# TikiLights.net
KiCad netlist of a schematic drawn in EAGLE
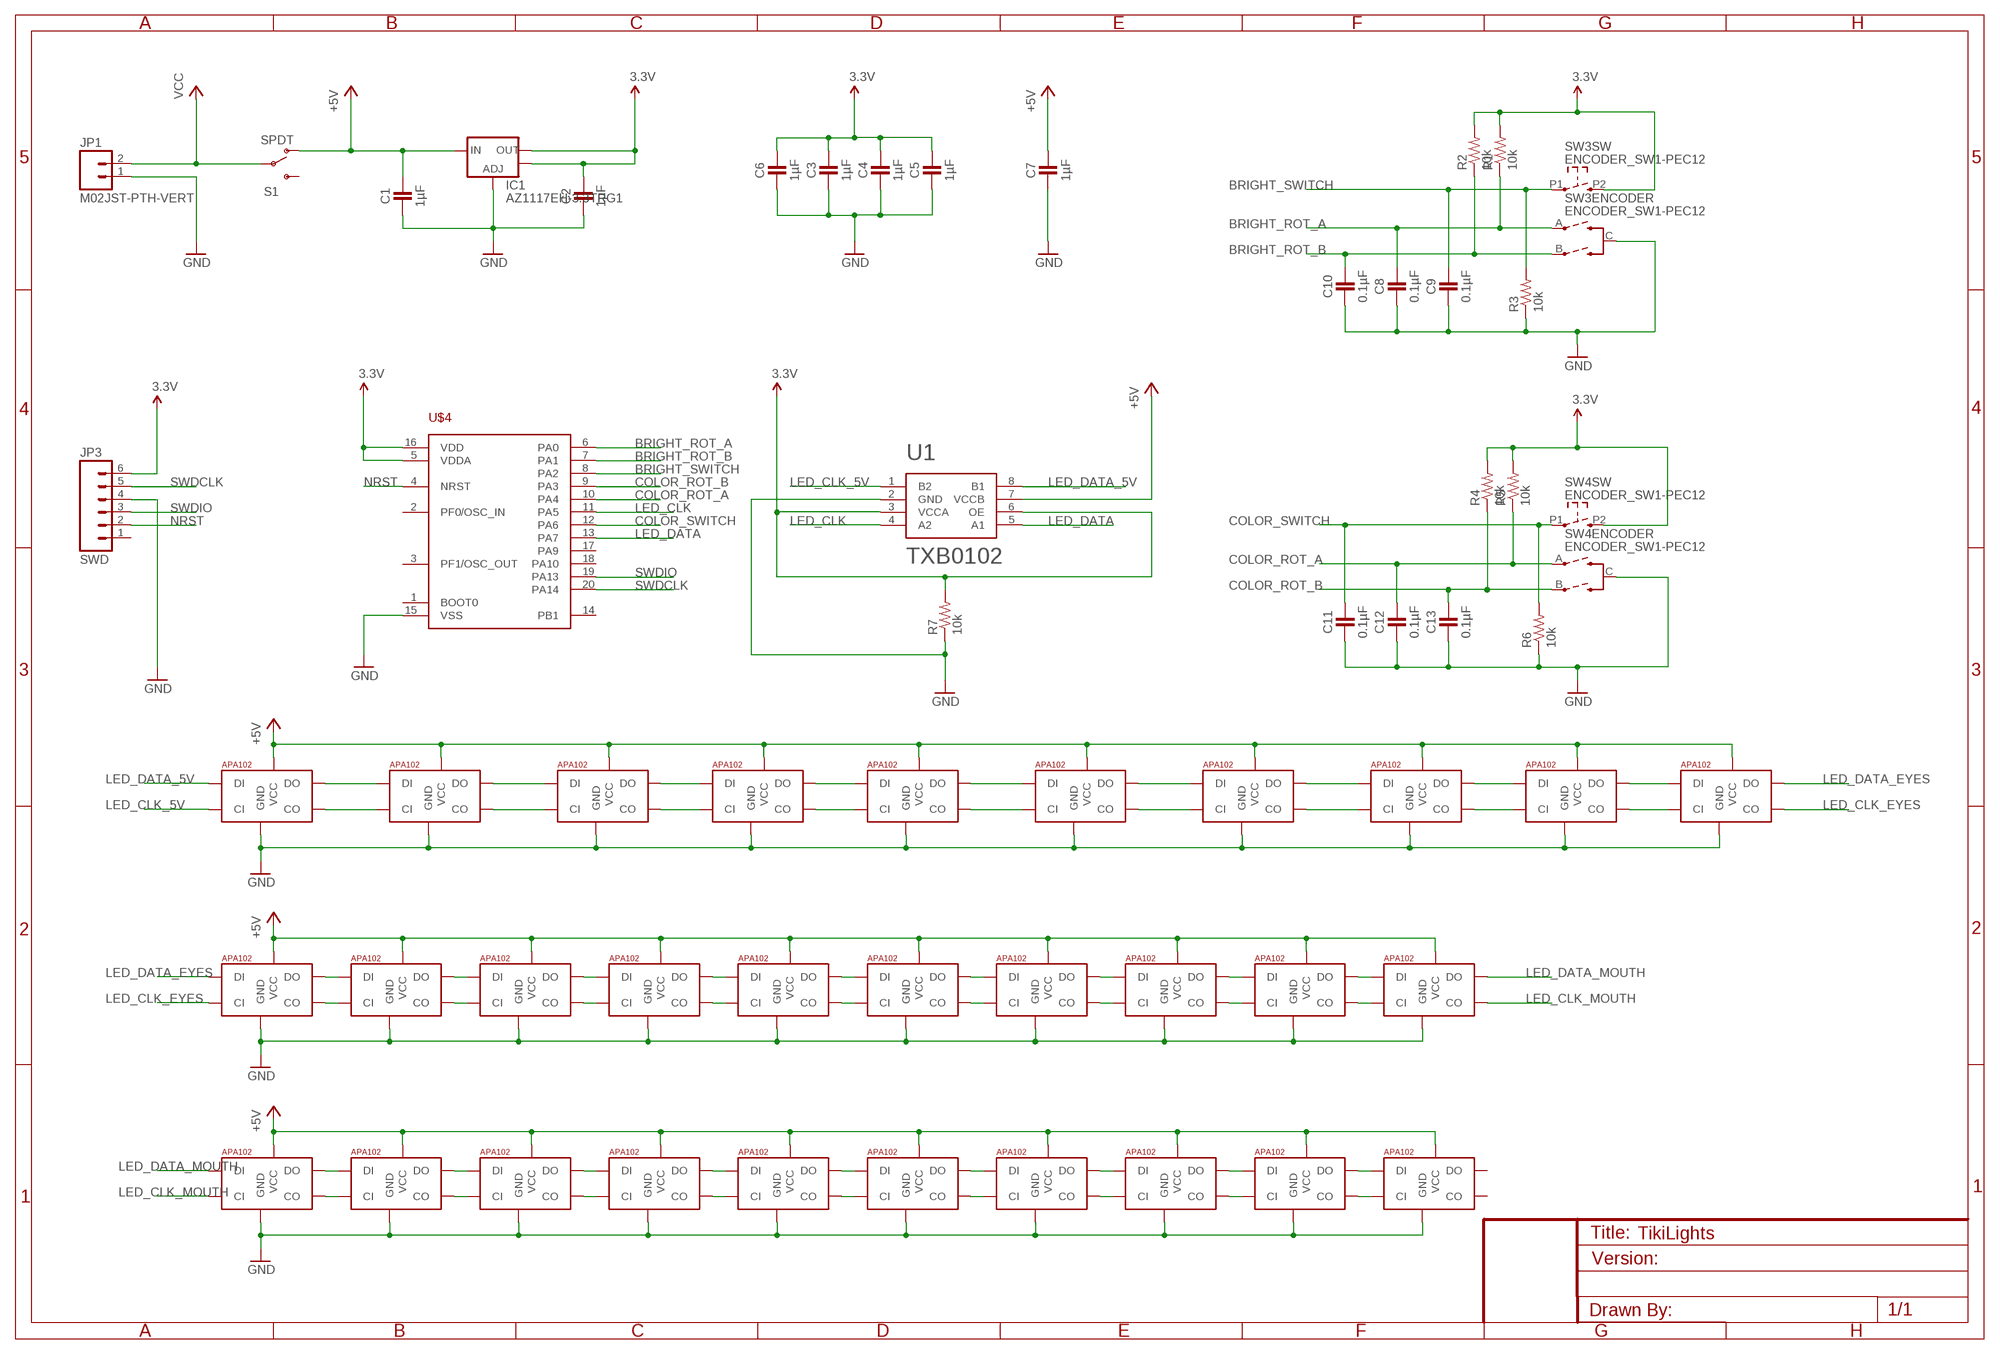
[diagram p0: schematic, sheet 1]

(export (version "E")
  (design (tool "Eeschema 10.0.6"))
  (components
    (comp (ref "C1")
      (value "1µF")
      (footprint "eagle-import:0603_CAP")
      (libsource (lib "eagle-import") (part "CAPACITOR0603_CAP"))
    )
    (comp (ref "C2")
      (value "1µF")
      (footprint "eagle-import:0603_CAP")
      (libsource (lib "eagle-import") (part "CAPACITOR0603_CAP"))
    )
    (comp (ref "C3")
      (value "1µF")
      (footprint "eagle-import:0603_CAP")
      (libsource (lib "eagle-import") (part "CAPACITOR0603_CAP"))
    )
    (comp (ref "C4")
      (value "1µF")
      (footprint "eagle-import:0603_CAP")
      (libsource (lib "eagle-import") (part "CAPACITOR0603_CAP"))
    )
    (comp (ref "C5")
      (value "1µF")
      (footprint "eagle-import:0603_CAP")
      (libsource (lib "eagle-import") (part "CAPACITOR0603_CAP"))
    )
    (comp (ref "C6")
      (value "1µF")
      (footprint "eagle-import:0603_CAP")
      (libsource (lib "eagle-import") (part "CAPACITOR0603_CAP"))
    )
    (comp (ref "C7")
      (value "1µF")
      (footprint "eagle-import:0603_CAP")
      (libsource (lib "eagle-import") (part "CAPACITOR0603_CAP"))
    )
    (comp (ref "C8")
      (value "0.1µF")
      (footprint "eagle-import:0603_CAP")
      (libsource (lib "eagle-import") (part "CAPACITOR0603_CAP"))
    )
    (comp (ref "C9")
      (value "0.1µF")
      (footprint "eagle-import:0603_CAP")
      (libsource (lib "eagle-import") (part "CAPACITOR0603_CAP"))
    )
    (comp (ref "C10")
      (value "0.1µF")
      (footprint "eagle-import:0603_CAP")
      (libsource (lib "eagle-import") (part "CAPACITOR0603_CAP"))
    )
    (comp (ref "C11")
      (value "0.1µF")
      (footprint "eagle-import:0603_CAP")
      (libsource (lib "eagle-import") (part "CAPACITOR0603_CAP"))
    )
    (comp (ref "C12")
      (value "0.1µF")
      (footprint "eagle-import:0603_CAP")
      (libsource (lib "eagle-import") (part "CAPACITOR0603_CAP"))
    )
    (comp (ref "C13")
      (value "0.1µF")
      (footprint "eagle-import:0603_CAP")
      (libsource (lib "eagle-import") (part "CAPACITOR0603_CAP"))
    )
    (comp (ref "IC1")
      (value "AZ1117EH-3.3TRG1")
      (footprint "eagle-import:SOT223")
      (libsource (lib "eagle-import") (part "V_REG_LM1117SOT223"))
    )
    (comp (ref "JP1")
      (value "M02JST-PTH-VERT")
      (footprint "eagle-import:JST-2-PTH-VERT")
      (libsource (lib "eagle-import") (part "M02JST-PTH-VERT"))
    )
    (comp (ref "JP3")
      (value "SWD")
      (footprint "eagle-import:MOLEX-1X6")
      (libsource (lib "eagle-import") (part "M06POLAR"))
    )
    (comp (ref "R1")
      (value "10k")
      (footprint "eagle-import:0603-RES")
      (libsource (lib "eagle-import") (part "RESISTOR0603"))
    )
    (comp (ref "R2")
      (value "10k")
      (footprint "eagle-import:0603-RES")
      (libsource (lib "eagle-import") (part "RESISTOR0603"))
    )
    (comp (ref "R3")
      (value "10k")
      (footprint "eagle-import:0603-RES")
      (libsource (lib "eagle-import") (part "RESISTOR0603"))
    )
    (comp (ref "R4")
      (value "10k")
      (footprint "eagle-import:0603-RES")
      (libsource (lib "eagle-import") (part "RESISTOR0603"))
    )
    (comp (ref "R5")
      (value "10k")
      (footprint "eagle-import:0603-RES")
      (libsource (lib "eagle-import") (part "RESISTOR0603"))
    )
    (comp (ref "R6")
      (value "10k")
      (footprint "eagle-import:0603-RES")
      (libsource (lib "eagle-import") (part "RESISTOR0603"))
    )
    (comp (ref "R7")
      (value "10k")
      (footprint "eagle-import:0603-RES")
      (libsource (lib "eagle-import") (part "RESISTOR0603"))
    )
    (comp (ref "S1")
      (value "SPDT")
      (footprint "eagle-import:SWITCH-SPDT")
      (libsource (lib "eagle-import") (part "SWITCH-SPDTPTH"))
    )
    (comp (ref "SW3")
      (value "ENCODER_SW1-PEC12")
      (footprint "eagle-import:PEC12_INCREMENTAL_ENCODER")
      (libsource (lib "eagle-import") (part "ENCODER_SW1-PEC12"))
    )
    (comp (ref "SW4")
      (value "ENCODER_SW1-PEC12")
      (footprint "eagle-import:PEC12_INCREMENTAL_ENCODER")
      (libsource (lib "eagle-import") (part "ENCODER_SW1-PEC12"))
    )
    (comp (ref "U$1")
      (value "APA1022020")
      (footprint "eagle-import:APA102_2020")
      (libsource (lib "eagle-import") (part "APA1022020"))
    )
    (comp (ref "U$2")
      (value "APA1022020")
      (footprint "eagle-import:APA102_2020")
      (libsource (lib "eagle-import") (part "APA1022020"))
    )
    (comp (ref "U$3")
      (value "APA1022020")
      (footprint "eagle-import:APA102_2020")
      (libsource (lib "eagle-import") (part "APA1022020"))
    )
    (comp (ref "U$4")
      (value "STM32F030F4")
      (footprint "eagle-import:TSSOP20")
      (libsource (lib "eagle-import") (part "STM32F030F4"))
    )
    (comp (ref "U$5")
      (value "APA1022020")
      (footprint "eagle-import:APA102_2020")
      (libsource (lib "eagle-import") (part "APA1022020"))
    )
    (comp (ref "U$6")
      (value "APA1022020")
      (footprint "eagle-import:APA102_2020")
      (libsource (lib "eagle-import") (part "APA1022020"))
    )
    (comp (ref "U$7")
      (value "APA1025050")
      (footprint "eagle-import:APA102_5050")
      (libsource (lib "eagle-import") (part "APA1025050"))
    )
    (comp (ref "U$8")
      (value "APA1025050")
      (footprint "eagle-import:APA102_5050")
      (libsource (lib "eagle-import") (part "APA1025050"))
    )
    (comp (ref "U$9")
      (value "APA1025050")
      (footprint "eagle-import:APA102_5050")
      (libsource (lib "eagle-import") (part "APA1025050"))
    )
    (comp (ref "U$10")
      (value "APA1025050")
      (footprint "eagle-import:APA102_5050")
      (libsource (lib "eagle-import") (part "APA1025050"))
    )
    (comp (ref "U$11")
      (value "APA1025050")
      (footprint "eagle-import:APA102_5050")
      (libsource (lib "eagle-import") (part "APA1025050"))
    )
    (comp (ref "U$12")
      (value "APA1025050")
      (footprint "eagle-import:APA102_5050")
      (libsource (lib "eagle-import") (part "APA1025050"))
    )
    (comp (ref "U$13")
      (value "APA1025050")
      (footprint "eagle-import:APA102_5050")
      (libsource (lib "eagle-import") (part "APA1025050"))
    )
    (comp (ref "U$14")
      (value "APA1025050")
      (footprint "eagle-import:APA102_5050")
      (libsource (lib "eagle-import") (part "APA1025050"))
    )
    (comp (ref "U$15")
      (value "APA1025050")
      (footprint "eagle-import:APA102_5050")
      (libsource (lib "eagle-import") (part "APA1025050"))
    )
    (comp (ref "U$16")
      (value "APA1025050")
      (footprint "eagle-import:APA102_5050")
      (libsource (lib "eagle-import") (part "APA1025050"))
    )
    (comp (ref "U$17")
      (value "APA1025050")
      (footprint "eagle-import:APA102_5050")
      (libsource (lib "eagle-import") (part "APA1025050"))
    )
    (comp (ref "U$18")
      (value "APA1025050")
      (footprint "eagle-import:APA102_5050")
      (libsource (lib "eagle-import") (part "APA1025050"))
    )
    (comp (ref "U$19")
      (value "APA1025050")
      (footprint "eagle-import:APA102_5050")
      (libsource (lib "eagle-import") (part "APA1025050"))
    )
    (comp (ref "U$20")
      (value "APA1025050")
      (footprint "eagle-import:APA102_5050")
      (libsource (lib "eagle-import") (part "APA1025050"))
    )
    (comp (ref "U$21")
      (value "APA1025050")
      (footprint "eagle-import:APA102_5050")
      (libsource (lib "eagle-import") (part "APA1025050"))
    )
    (comp (ref "U$22")
      (value "APA1025050")
      (footprint "eagle-import:APA102_5050")
      (libsource (lib "eagle-import") (part "APA1025050"))
    )
    (comp (ref "U$23")
      (value "APA1025050")
      (footprint "eagle-import:APA102_5050")
      (libsource (lib "eagle-import") (part "APA1025050"))
    )
    (comp (ref "U$24")
      (value "APA1025050")
      (footprint "eagle-import:APA102_5050")
      (libsource (lib "eagle-import") (part "APA1025050"))
    )
    (comp (ref "U$25")
      (value "APA1025050")
      (footprint "eagle-import:APA102_5050")
      (libsource (lib "eagle-import") (part "APA1025050"))
    )
    (comp (ref "U$26")
      (value "APA1025050")
      (footprint "eagle-import:APA102_5050")
      (libsource (lib "eagle-import") (part "APA1025050"))
    )
    (comp (ref "U$27")
      (value "APA1022020")
      (footprint "eagle-import:APA102_2020")
      (libsource (lib "eagle-import") (part "APA1022020"))
    )
    (comp (ref "U$28")
      (value "APA1022020")
      (footprint "eagle-import:APA102_2020")
      (libsource (lib "eagle-import") (part "APA1022020"))
    )
    (comp (ref "U$29")
      (value "APA1022020")
      (footprint "eagle-import:APA102_2020")
      (libsource (lib "eagle-import") (part "APA1022020"))
    )
    (comp (ref "U$30")
      (value "APA1022020")
      (footprint "eagle-import:APA102_2020")
      (libsource (lib "eagle-import") (part "APA1022020"))
    )
    (comp (ref "U$31")
      (value "APA1022020")
      (footprint "eagle-import:APA102_2020")
      (libsource (lib "eagle-import") (part "APA1022020"))
    )
    (comp (ref "U1")
      (value "TXB0102")
      (footprint "eagle-import:SOP50P310X90-8N")
      (fields (field (name "MF") "Texas Instruments"))
      (libsource (lib "eagle-import") (part "TXB0102"))
    )
  )
  (nets
    (net (code "1") (name "+5V") (class "Default")
      (node (ref "C1") (pin "1") (pinfunction "1_1") (pintype "bidirectional"))
      (node (ref "C7") (pin "1") (pinfunction "1_1") (pintype "bidirectional"))
      (node (ref "IC1") (pin "3") (pinfunction "IN_3") (pintype "input"))
      (node (ref "S1") (pin "1") (pinfunction "O_1") (pintype "passive"))
      (node (ref "U$1") (pin "V_CC") (pinfunction "VCC_V_CC") (pintype "bidirectional"))
      (node (ref "U$10") (pin "1") (pinfunction "VCC_1") (pintype "bidirectional"))
      (node (ref "U$11") (pin "1") (pinfunction "VCC_1") (pintype "bidirectional"))
      (node (ref "U$12") (pin "1") (pinfunction "VCC_1") (pintype "bidirectional"))
      (node (ref "U$13") (pin "1") (pinfunction "VCC_1") (pintype "bidirectional"))
      (node (ref "U$14") (pin "1") (pinfunction "VCC_1") (pintype "bidirectional"))
      (node (ref "U$15") (pin "1") (pinfunction "VCC_1") (pintype "bidirectional"))
      (node (ref "U$16") (pin "1") (pinfunction "VCC_1") (pintype "bidirectional"))
      (node (ref "U$17") (pin "1") (pinfunction "VCC_1") (pintype "bidirectional"))
      (node (ref "U$18") (pin "1") (pinfunction "VCC_1") (pintype "bidirectional"))
      (node (ref "U$19") (pin "1") (pinfunction "VCC_1") (pintype "bidirectional"))
      (node (ref "U$2") (pin "V_CC") (pinfunction "VCC_V_CC") (pintype "bidirectional"))
      (node (ref "U$20") (pin "1") (pinfunction "VCC_1") (pintype "bidirectional"))
      (node (ref "U$21") (pin "1") (pinfunction "VCC_1") (pintype "bidirectional"))
      (node (ref "U$22") (pin "1") (pinfunction "VCC_1") (pintype "bidirectional"))
      (node (ref "U$23") (pin "1") (pinfunction "VCC_1") (pintype "bidirectional"))
      (node (ref "U$24") (pin "1") (pinfunction "VCC_1") (pintype "bidirectional"))
      (node (ref "U$25") (pin "1") (pinfunction "VCC_1") (pintype "bidirectional"))
      (node (ref "U$26") (pin "1") (pinfunction "VCC_1") (pintype "bidirectional"))
      (node (ref "U$27") (pin "V_CC") (pinfunction "VCC_V_CC") (pintype "bidirectional"))
      (node (ref "U$28") (pin "V_CC") (pinfunction "VCC_V_CC") (pintype "bidirectional"))
      (node (ref "U$29") (pin "V_CC") (pinfunction "VCC_V_CC") (pintype "bidirectional"))
      (node (ref "U$3") (pin "V_CC") (pinfunction "VCC_V_CC") (pintype "bidirectional"))
      (node (ref "U$30") (pin "V_CC") (pinfunction "VCC_V_CC") (pintype "bidirectional"))
      (node (ref "U$31") (pin "V_CC") (pinfunction "VCC_V_CC") (pintype "bidirectional"))
      (node (ref "U$5") (pin "V_CC") (pinfunction "VCC_V_CC") (pintype "bidirectional"))
      (node (ref "U$6") (pin "V_CC") (pinfunction "VCC_V_CC") (pintype "bidirectional"))
      (node (ref "U$7") (pin "1") (pinfunction "VCC_1") (pintype "bidirectional"))
      (node (ref "U$8") (pin "1") (pinfunction "VCC_1") (pintype "bidirectional"))
      (node (ref "U$9") (pin "1") (pinfunction "VCC_1") (pintype "bidirectional"))
      (node (ref "U1") (pin "7") (pinfunction "VCCB_7") (pintype "bidirectional"))
    )
    (net (code "2") (name "/BRIGHT_ROT_A") (class "Default")
      (node (ref "C8") (pin "1") (pinfunction "1_1") (pintype "bidirectional"))
      (node (ref "R1") (pin "1") (pinfunction "1_1") (pintype "passive"))
      (node (ref "SW3") (pin "A") (pinfunction "A_A") (pintype "passive"))
      (node (ref "U$4") (pin "6") (pinfunction "PA0_6") (pintype "bidirectional"))
    )
    (net (code "3") (name "/BRIGHT_ROT_B") (class "Default")
      (node (ref "C10") (pin "1") (pinfunction "1_1") (pintype "bidirectional"))
      (node (ref "R2") (pin "1") (pinfunction "1_1") (pintype "passive"))
      (node (ref "SW3") (pin "B") (pinfunction "B_B") (pintype "passive"))
      (node (ref "U$4") (pin "7") (pinfunction "PA1_7") (pintype "bidirectional"))
    )
    (net (code "4") (name "/BRIGHT_SWITCH") (class "Default")
      (node (ref "C9") (pin "1") (pinfunction "1_1") (pintype "bidirectional"))
      (node (ref "R3") (pin "2") (pinfunction "2_2") (pintype "passive"))
      (node (ref "SW3") (pin "P1") (pinfunction "1_P1") (pintype "passive"))
      (node (ref "U$4") (pin "8") (pinfunction "PA2_8") (pintype "bidirectional"))
    )
    (net (code "5") (name "/COLOR_ROT_A") (class "Default")
      (node (ref "C12") (pin "1") (pinfunction "1_1") (pintype "bidirectional"))
      (node (ref "R5") (pin "1") (pinfunction "1_1") (pintype "passive"))
      (node (ref "SW4") (pin "A") (pinfunction "A_A") (pintype "passive"))
      (node (ref "U$4") (pin "10") (pinfunction "PA4_10") (pintype "bidirectional"))
    )
    (net (code "6") (name "/COLOR_ROT_B") (class "Default")
      (node (ref "C13") (pin "1") (pinfunction "1_1") (pintype "bidirectional"))
      (node (ref "R4") (pin "1") (pinfunction "1_1") (pintype "passive"))
      (node (ref "SW4") (pin "B") (pinfunction "B_B") (pintype "passive"))
      (node (ref "U$4") (pin "9") (pinfunction "PA3_9") (pintype "bidirectional"))
    )
    (net (code "7") (name "/COLOR_SWITCH") (class "Default")
      (node (ref "C11") (pin "1") (pinfunction "1_1") (pintype "bidirectional"))
      (node (ref "R6") (pin "2") (pinfunction "2_2") (pintype "passive"))
      (node (ref "SW4") (pin "P1") (pinfunction "1_P1") (pintype "passive"))
      (node (ref "U$4") (pin "12") (pinfunction "PA6_12") (pintype "bidirectional"))
    )
    (net (code "8") (name "/LED_CLK") (class "Default")
      (node (ref "U$4") (pin "11") (pinfunction "PA5_11") (pintype "bidirectional"))
      (node (ref "U1") (pin "4") (pinfunction "A2_4") (pintype "bidirectional"))
    )
    (net (code "9") (name "/LED_CLK_5V") (class "Default")
      (node (ref "U$1") (pin "C_IN") (pinfunction "CI_C_IN") (pintype "bidirectional"))
      (node (ref "U1") (pin "1") (pinfunction "B2_1") (pintype "bidirectional"))
    )
    (net (code "10") (name "/LED_CLK_EYES") (class "Default")
      (node (ref "U$31") (pin "CL_OUT") (pinfunction "CO_CL_OUT") (pintype "bidirectional"))
      (node (ref "U$7") (pin "5") (pinfunction "CI_5") (pintype "bidirectional"))
    )
    (net (code "11") (name "/LED_CLK_MOUTH") (class "Default")
      (node (ref "U$16") (pin "2") (pinfunction "CO_2") (pintype "bidirectional"))
      (node (ref "U$17") (pin "5") (pinfunction "CI_5") (pintype "bidirectional"))
    )
    (net (code "12") (name "/LED_DATA") (class "Default")
      (node (ref "U$4") (pin "13") (pinfunction "PA7_13") (pintype "bidirectional"))
      (node (ref "U1") (pin "5") (pinfunction "A1_5") (pintype "bidirectional"))
    )
    (net (code "13") (name "/LED_DATA_5V") (class "Default")
      (node (ref "U$1") (pin "D_IN") (pinfunction "DI_D_IN") (pintype "bidirectional"))
      (node (ref "U1") (pin "8") (pinfunction "B1_8") (pintype "bidirectional"))
    )
    (net (code "14") (name "/LED_DATA_EYES") (class "Default")
      (node (ref "U$31") (pin "D_OUT") (pinfunction "DO_D_OUT") (pintype "bidirectional"))
      (node (ref "U$7") (pin "4") (pinfunction "DI_4") (pintype "bidirectional"))
    )
    (net (code "15") (name "/LED_DATA_MOUTH") (class "Default")
      (node (ref "U$16") (pin "3") (pinfunction "DO_3") (pintype "bidirectional"))
      (node (ref "U$17") (pin "4") (pinfunction "DI_4") (pintype "bidirectional"))
    )
    (net (code "16") (name "/NRST") (class "Default")
      (node (ref "JP3") (pin "2") (pinfunction "2_2") (pintype "passive"))
      (node (ref "U$4") (pin "4") (pinfunction "NRST_4") (pintype "bidirectional"))
    )
    (net (code "17") (name "/SWDCLK") (class "Default")
      (node (ref "JP3") (pin "5") (pinfunction "5_5") (pintype "passive"))
      (node (ref "U$4") (pin "20") (pinfunction "PA14_20") (pintype "bidirectional"))
    )
    (net (code "18") (name "/SWDIO") (class "Default")
      (node (ref "JP3") (pin "3") (pinfunction "3_3") (pintype "passive"))
      (node (ref "U$4") (pin "19") (pinfunction "PA13_19") (pintype "bidirectional"))
    )
    (net (code "19") (name "3.3V") (class "Default")
      (node (ref "C2") (pin "1") (pinfunction "1_1") (pintype "bidirectional"))
      (node (ref "C3") (pin "1") (pinfunction "1_1") (pintype "bidirectional"))
      (node (ref "C4") (pin "1") (pinfunction "1_1") (pintype "bidirectional"))
      (node (ref "C5") (pin "1") (pinfunction "1_1") (pintype "bidirectional"))
      (node (ref "C6") (pin "1") (pinfunction "1_1") (pintype "bidirectional"))
      (node (ref "IC1") (pin "2") (pinfunction "OUT_2") (pintype "output"))
      (node (ref "IC1") (pin "4") (pinfunction "OUT_4") (pintype "output"))
      (node (ref "JP3") (pin "6") (pinfunction "6_6") (pintype "passive"))
      (node (ref "R1") (pin "2") (pinfunction "2_2") (pintype "passive"))
      (node (ref "R2") (pin "2") (pinfunction "2_2") (pintype "passive"))
      (node (ref "R4") (pin "2") (pinfunction "2_2") (pintype "passive"))
      (node (ref "R5") (pin "2") (pinfunction "2_2") (pintype "passive"))
      (node (ref "R7") (pin "2") (pinfunction "2_2") (pintype "passive"))
      (node (ref "SW3") (pin "P2") (pinfunction "2_P2") (pintype "passive"))
      (node (ref "SW4") (pin "P2") (pinfunction "2_P2") (pintype "passive"))
      (node (ref "U$4") (pin "16") (pinfunction "VDD_16") (pintype "bidirectional"))
      (node (ref "U$4") (pin "5") (pinfunction "VDDA_5") (pintype "bidirectional"))
      (node (ref "U1") (pin "3") (pinfunction "VCCA_3") (pintype "bidirectional"))
      (node (ref "U1") (pin "6") (pinfunction "OE_6") (pintype "bidirectional"))
    )
    (net (code "20") (name "GND") (class "Default")
      (node (ref "C1") (pin "2") (pinfunction "2_2") (pintype "bidirectional"))
      (node (ref "C10") (pin "2") (pinfunction "2_2") (pintype "bidirectional"))
      (node (ref "C11") (pin "2") (pinfunction "2_2") (pintype "bidirectional"))
      (node (ref "C12") (pin "2") (pinfunction "2_2") (pintype "bidirectional"))
      (node (ref "C13") (pin "2") (pinfunction "2_2") (pintype "bidirectional"))
      (node (ref "C2") (pin "2") (pinfunction "2_2") (pintype "bidirectional"))
      (node (ref "C3") (pin "2") (pinfunction "2_2") (pintype "bidirectional"))
      (node (ref "C4") (pin "2") (pinfunction "2_2") (pintype "bidirectional"))
      (node (ref "C5") (pin "2") (pinfunction "2_2") (pintype "bidirectional"))
      (node (ref "C6") (pin "2") (pinfunction "2_2") (pintype "bidirectional"))
      (node (ref "C7") (pin "2") (pinfunction "2_2") (pintype "bidirectional"))
      (node (ref "C8") (pin "2") (pinfunction "2_2") (pintype "bidirectional"))
      (node (ref "C9") (pin "2") (pinfunction "2_2") (pintype "bidirectional"))
      (node (ref "IC1") (pin "1") (pinfunction "ADJ_1") (pintype "input"))
      (node (ref "JP1") (pin "1") (pinfunction "1_1") (pintype "passive"))
      (node (ref "JP3") (pin "4") (pinfunction "4_4") (pintype "passive"))
      (node (ref "R3") (pin "1") (pinfunction "1_1") (pintype "passive"))
      (node (ref "R6") (pin "1") (pinfunction "1_1") (pintype "passive"))
      (node (ref "R7") (pin "1") (pinfunction "1_1") (pintype "passive"))
      (node (ref "SW3") (pin "C") (pinfunction "C_C") (pintype "passive"))
      (node (ref "SW4") (pin "C") (pinfunction "C_C") (pintype "passive"))
      (node (ref "U$1") (pin "GND") (pinfunction "GND_GND") (pintype "bidirectional"))
      (node (ref "U$10") (pin "6") (pinfunction "GND_6") (pintype "bidirectional"))
      (node (ref "U$11") (pin "6") (pinfunction "GND_6") (pintype "bidirectional"))
      (node (ref "U$12") (pin "6") (pinfunction "GND_6") (pintype "bidirectional"))
      (node (ref "U$13") (pin "6") (pinfunction "GND_6") (pintype "bidirectional"))
      (node (ref "U$14") (pin "6") (pinfunction "GND_6") (pintype "bidirectional"))
      (node (ref "U$15") (pin "6") (pinfunction "GND_6") (pintype "bidirectional"))
      (node (ref "U$16") (pin "6") (pinfunction "GND_6") (pintype "bidirectional"))
      (node (ref "U$17") (pin "6") (pinfunction "GND_6") (pintype "bidirectional"))
      (node (ref "U$18") (pin "6") (pinfunction "GND_6") (pintype "bidirectional"))
      (node (ref "U$19") (pin "6") (pinfunction "GND_6") (pintype "bidirectional"))
      (node (ref "U$2") (pin "GND") (pinfunction "GND_GND") (pintype "bidirectional"))
      (node (ref "U$20") (pin "6") (pinfunction "GND_6") (pintype "bidirectional"))
      (node (ref "U$21") (pin "6") (pinfunction "GND_6") (pintype "bidirectional"))
      (node (ref "U$22") (pin "6") (pinfunction "GND_6") (pintype "bidirectional"))
      (node (ref "U$23") (pin "6") (pinfunction "GND_6") (pintype "bidirectional"))
      (node (ref "U$24") (pin "6") (pinfunction "GND_6") (pintype "bidirectional"))
      (node (ref "U$25") (pin "6") (pinfunction "GND_6") (pintype "bidirectional"))
      (node (ref "U$26") (pin "6") (pinfunction "GND_6") (pintype "bidirectional"))
      (node (ref "U$27") (pin "GND") (pinfunction "GND_GND") (pintype "bidirectional"))
      (node (ref "U$28") (pin "GND") (pinfunction "GND_GND") (pintype "bidirectional"))
      (node (ref "U$29") (pin "GND") (pinfunction "GND_GND") (pintype "bidirectional"))
      (node (ref "U$3") (pin "GND") (pinfunction "GND_GND") (pintype "bidirectional"))
      (node (ref "U$30") (pin "GND") (pinfunction "GND_GND") (pintype "bidirectional"))
      (node (ref "U$31") (pin "GND") (pinfunction "GND_GND") (pintype "bidirectional"))
      (node (ref "U$4") (pin "15") (pinfunction "VSS_15") (pintype "bidirectional"))
      (node (ref "U$5") (pin "GND") (pinfunction "GND_GND") (pintype "bidirectional"))
      (node (ref "U$6") (pin "GND") (pinfunction "GND_GND") (pintype "bidirectional"))
      (node (ref "U$7") (pin "6") (pinfunction "GND_6") (pintype "bidirectional"))
      (node (ref "U$8") (pin "6") (pinfunction "GND_6") (pintype "bidirectional"))
      (node (ref "U$9") (pin "6") (pinfunction "GND_6") (pintype "bidirectional"))
      (node (ref "U1") (pin "2") (pinfunction "GND_2") (pintype "bidirectional"))
    )
    (net (code "21") (name "Net-(U$1-CO)") (class "Default")
      (node (ref "U$1") (pin "CL_OUT") (pinfunction "CO_CL_OUT") (pintype "bidirectional"))
      (node (ref "U$2") (pin "C_IN") (pinfunction "CI_C_IN") (pintype "bidirectional"))
    )
    (net (code "22") (name "Net-(U$1-DO)") (class "Default")
      (node (ref "U$1") (pin "D_OUT") (pinfunction "DO_D_OUT") (pintype "bidirectional"))
      (node (ref "U$2") (pin "D_IN") (pinfunction "DI_D_IN") (pintype "bidirectional"))
    )
    (net (code "23") (name "Net-(U$2-CO)") (class "Default")
      (node (ref "U$2") (pin "CL_OUT") (pinfunction "CO_CL_OUT") (pintype "bidirectional"))
      (node (ref "U$3") (pin "C_IN") (pinfunction "CI_C_IN") (pintype "bidirectional"))
    )
    (net (code "24") (name "Net-(U$2-DO)") (class "Default")
      (node (ref "U$2") (pin "D_OUT") (pinfunction "DO_D_OUT") (pintype "bidirectional"))
      (node (ref "U$3") (pin "D_IN") (pinfunction "DI_D_IN") (pintype "bidirectional"))
    )
    (net (code "25") (name "Net-(U$3-CO)") (class "Default")
      (node (ref "U$3") (pin "CL_OUT") (pinfunction "CO_CL_OUT") (pintype "bidirectional"))
      (node (ref "U$5") (pin "C_IN") (pinfunction "CI_C_IN") (pintype "bidirectional"))
    )
    (net (code "26") (name "Net-(U$3-DO)") (class "Default")
      (node (ref "U$3") (pin "D_OUT") (pinfunction "DO_D_OUT") (pintype "bidirectional"))
      (node (ref "U$5") (pin "D_IN") (pinfunction "DI_D_IN") (pintype "bidirectional"))
    )
    (net (code "27") (name "Net-(U$5-CO)") (class "Default")
      (node (ref "U$5") (pin "CL_OUT") (pinfunction "CO_CL_OUT") (pintype "bidirectional"))
      (node (ref "U$6") (pin "C_IN") (pinfunction "CI_C_IN") (pintype "bidirectional"))
    )
    (net (code "28") (name "Net-(U$5-DO)") (class "Default")
      (node (ref "U$5") (pin "D_OUT") (pinfunction "DO_D_OUT") (pintype "bidirectional"))
      (node (ref "U$6") (pin "D_IN") (pinfunction "DI_D_IN") (pintype "bidirectional"))
    )
    (net (code "29") (name "Net-(U$7-CO)") (class "Default")
      (node (ref "U$7") (pin "2") (pinfunction "CO_2") (pintype "bidirectional"))
      (node (ref "U$8") (pin "5") (pinfunction "CI_5") (pintype "bidirectional"))
    )
    (net (code "30") (name "Net-(U$7-DO)") (class "Default")
      (node (ref "U$7") (pin "3") (pinfunction "DO_3") (pintype "bidirectional"))
      (node (ref "U$8") (pin "4") (pinfunction "DI_4") (pintype "bidirectional"))
    )
    (net (code "31") (name "Net-(U$8-CO)") (class "Default")
      (node (ref "U$8") (pin "2") (pinfunction "CO_2") (pintype "bidirectional"))
      (node (ref "U$9") (pin "5") (pinfunction "CI_5") (pintype "bidirectional"))
    )
    (net (code "32") (name "Net-(U$8-DO)") (class "Default")
      (node (ref "U$8") (pin "3") (pinfunction "DO_3") (pintype "bidirectional"))
      (node (ref "U$9") (pin "4") (pinfunction "DI_4") (pintype "bidirectional"))
    )
    (net (code "33") (name "Net-(U$10-CI)") (class "Default")
      (node (ref "U$10") (pin "5") (pinfunction "CI_5") (pintype "bidirectional"))
      (node (ref "U$9") (pin "2") (pinfunction "CO_2") (pintype "bidirectional"))
    )
    (net (code "34") (name "Net-(U$10-CO)") (class "Default")
      (node (ref "U$10") (pin "2") (pinfunction "CO_2") (pintype "bidirectional"))
      (node (ref "U$11") (pin "5") (pinfunction "CI_5") (pintype "bidirectional"))
    )
    (net (code "35") (name "Net-(U$10-DI)") (class "Default")
      (node (ref "U$10") (pin "4") (pinfunction "DI_4") (pintype "bidirectional"))
      (node (ref "U$9") (pin "3") (pinfunction "DO_3") (pintype "bidirectional"))
    )
    (net (code "36") (name "Net-(U$10-DO)") (class "Default")
      (node (ref "U$10") (pin "3") (pinfunction "DO_3") (pintype "bidirectional"))
      (node (ref "U$11") (pin "4") (pinfunction "DI_4") (pintype "bidirectional"))
    )
    (net (code "37") (name "Net-(U$11-CO)") (class "Default")
      (node (ref "U$11") (pin "2") (pinfunction "CO_2") (pintype "bidirectional"))
      (node (ref "U$12") (pin "5") (pinfunction "CI_5") (pintype "bidirectional"))
    )
    (net (code "38") (name "Net-(U$11-DO)") (class "Default")
      (node (ref "U$11") (pin "3") (pinfunction "DO_3") (pintype "bidirectional"))
      (node (ref "U$12") (pin "4") (pinfunction "DI_4") (pintype "bidirectional"))
    )
    (net (code "39") (name "Net-(U$12-CO)") (class "Default")
      (node (ref "U$12") (pin "2") (pinfunction "CO_2") (pintype "bidirectional"))
      (node (ref "U$13") (pin "5") (pinfunction "CI_5") (pintype "bidirectional"))
    )
    (net (code "40") (name "Net-(U$12-DO)") (class "Default")
      (node (ref "U$12") (pin "3") (pinfunction "DO_3") (pintype "bidirectional"))
      (node (ref "U$13") (pin "4") (pinfunction "DI_4") (pintype "bidirectional"))
    )
    (net (code "41") (name "Net-(U$13-CO)") (class "Default")
      (node (ref "U$13") (pin "2") (pinfunction "CO_2") (pintype "bidirectional"))
      (node (ref "U$14") (pin "5") (pinfunction "CI_5") (pintype "bidirectional"))
    )
    (net (code "42") (name "Net-(U$13-DO)") (class "Default")
      (node (ref "U$13") (pin "3") (pinfunction "DO_3") (pintype "bidirectional"))
      (node (ref "U$14") (pin "4") (pinfunction "DI_4") (pintype "bidirectional"))
    )
    (net (code "43") (name "Net-(U$14-CO)") (class "Default")
      (node (ref "U$14") (pin "2") (pinfunction "CO_2") (pintype "bidirectional"))
      (node (ref "U$15") (pin "5") (pinfunction "CI_5") (pintype "bidirectional"))
    )
    (net (code "44") (name "Net-(U$14-DO)") (class "Default")
      (node (ref "U$14") (pin "3") (pinfunction "DO_3") (pintype "bidirectional"))
      (node (ref "U$15") (pin "4") (pinfunction "DI_4") (pintype "bidirectional"))
    )
    (net (code "45") (name "Net-(U$15-CO)") (class "Default")
      (node (ref "U$15") (pin "2") (pinfunction "CO_2") (pintype "bidirectional"))
      (node (ref "U$16") (pin "5") (pinfunction "CI_5") (pintype "bidirectional"))
    )
    (net (code "46") (name "Net-(U$15-DO)") (class "Default")
      (node (ref "U$15") (pin "3") (pinfunction "DO_3") (pintype "bidirectional"))
      (node (ref "U$16") (pin "4") (pinfunction "DI_4") (pintype "bidirectional"))
    )
    (net (code "47") (name "Net-(U$17-CO)") (class "Default")
      (node (ref "U$17") (pin "2") (pinfunction "CO_2") (pintype "bidirectional"))
      (node (ref "U$18") (pin "5") (pinfunction "CI_5") (pintype "bidirectional"))
    )
    (net (code "48") (name "Net-(U$17-DO)") (class "Default")
      (node (ref "U$17") (pin "3") (pinfunction "DO_3") (pintype "bidirectional"))
      (node (ref "U$18") (pin "4") (pinfunction "DI_4") (pintype "bidirectional"))
    )
    (net (code "49") (name "Net-(U$18-CO)") (class "Default")
      (node (ref "U$18") (pin "2") (pinfunction "CO_2") (pintype "bidirectional"))
      (node (ref "U$19") (pin "5") (pinfunction "CI_5") (pintype "bidirectional"))
    )
    (net (code "50") (name "Net-(U$18-DO)") (class "Default")
      (node (ref "U$18") (pin "3") (pinfunction "DO_3") (pintype "bidirectional"))
      (node (ref "U$19") (pin "4") (pinfunction "DI_4") (pintype "bidirectional"))
    )
    (net (code "51") (name "Net-(U$19-CO)") (class "Default")
      (node (ref "U$19") (pin "2") (pinfunction "CO_2") (pintype "bidirectional"))
      (node (ref "U$20") (pin "5") (pinfunction "CI_5") (pintype "bidirectional"))
    )
    (net (code "52") (name "Net-(U$19-DO)") (class "Default")
      (node (ref "U$19") (pin "3") (pinfunction "DO_3") (pintype "bidirectional"))
      (node (ref "U$20") (pin "4") (pinfunction "DI_4") (pintype "bidirectional"))
    )
    (net (code "53") (name "Net-(U$20-CO)") (class "Default")
      (node (ref "U$20") (pin "2") (pinfunction "CO_2") (pintype "bidirectional"))
      (node (ref "U$21") (pin "5") (pinfunction "CI_5") (pintype "bidirectional"))
    )
    (net (code "54") (name "Net-(U$20-DO)") (class "Default")
      (node (ref "U$20") (pin "3") (pinfunction "DO_3") (pintype "bidirectional"))
      (node (ref "U$21") (pin "4") (pinfunction "DI_4") (pintype "bidirectional"))
    )
    (net (code "55") (name "Net-(U$21-CO)") (class "Default")
      (node (ref "U$21") (pin "2") (pinfunction "CO_2") (pintype "bidirectional"))
      (node (ref "U$22") (pin "5") (pinfunction "CI_5") (pintype "bidirectional"))
    )
    (net (code "56") (name "Net-(U$21-DO)") (class "Default")
      (node (ref "U$21") (pin "3") (pinfunction "DO_3") (pintype "bidirectional"))
      (node (ref "U$22") (pin "4") (pinfunction "DI_4") (pintype "bidirectional"))
    )
    (net (code "57") (name "Net-(U$22-CO)") (class "Default")
      (node (ref "U$22") (pin "2") (pinfunction "CO_2") (pintype "bidirectional"))
      (node (ref "U$23") (pin "5") (pinfunction "CI_5") (pintype "bidirectional"))
    )
    (net (code "58") (name "Net-(U$22-DO)") (class "Default")
      (node (ref "U$22") (pin "3") (pinfunction "DO_3") (pintype "bidirectional"))
      (node (ref "U$23") (pin "4") (pinfunction "DI_4") (pintype "bidirectional"))
    )
    (net (code "59") (name "Net-(U$23-CO)") (class "Default")
      (node (ref "U$23") (pin "2") (pinfunction "CO_2") (pintype "bidirectional"))
      (node (ref "U$24") (pin "5") (pinfunction "CI_5") (pintype "bidirectional"))
    )
    (net (code "60") (name "Net-(U$23-DO)") (class "Default")
      (node (ref "U$23") (pin "3") (pinfunction "DO_3") (pintype "bidirectional"))
      (node (ref "U$24") (pin "4") (pinfunction "DI_4") (pintype "bidirectional"))
    )
    (net (code "61") (name "Net-(U$24-CO)") (class "Default")
      (node (ref "U$24") (pin "2") (pinfunction "CO_2") (pintype "bidirectional"))
      (node (ref "U$25") (pin "5") (pinfunction "CI_5") (pintype "bidirectional"))
    )
    (net (code "62") (name "Net-(U$24-DO)") (class "Default")
      (node (ref "U$24") (pin "3") (pinfunction "DO_3") (pintype "bidirectional"))
      (node (ref "U$25") (pin "4") (pinfunction "DI_4") (pintype "bidirectional"))
    )
    (net (code "63") (name "Net-(U$25-CO)") (class "Default")
      (node (ref "U$25") (pin "2") (pinfunction "CO_2") (pintype "bidirectional"))
      (node (ref "U$26") (pin "5") (pinfunction "CI_5") (pintype "bidirectional"))
    )
    (net (code "64") (name "Net-(U$25-DO)") (class "Default")
      (node (ref "U$25") (pin "3") (pinfunction "DO_3") (pintype "bidirectional"))
      (node (ref "U$26") (pin "4") (pinfunction "DI_4") (pintype "bidirectional"))
    )
    (net (code "65") (name "Net-(U$27-CI)") (class "Default")
      (node (ref "U$27") (pin "C_IN") (pinfunction "CI_C_IN") (pintype "bidirectional"))
      (node (ref "U$6") (pin "CL_OUT") (pinfunction "CO_CL_OUT") (pintype "bidirectional"))
    )
    (net (code "66") (name "Net-(U$27-CO)") (class "Default")
      (node (ref "U$27") (pin "CL_OUT") (pinfunction "CO_CL_OUT") (pintype "bidirectional"))
      (node (ref "U$28") (pin "C_IN") (pinfunction "CI_C_IN") (pintype "bidirectional"))
    )
    (net (code "67") (name "Net-(U$27-DI)") (class "Default")
      (node (ref "U$27") (pin "D_IN") (pinfunction "DI_D_IN") (pintype "bidirectional"))
      (node (ref "U$6") (pin "D_OUT") (pinfunction "DO_D_OUT") (pintype "bidirectional"))
    )
    (net (code "68") (name "Net-(U$27-DO)") (class "Default")
      (node (ref "U$27") (pin "D_OUT") (pinfunction "DO_D_OUT") (pintype "bidirectional"))
      (node (ref "U$28") (pin "D_IN") (pinfunction "DI_D_IN") (pintype "bidirectional"))
    )
    (net (code "69") (name "Net-(U$28-CO)") (class "Default")
      (node (ref "U$28") (pin "CL_OUT") (pinfunction "CO_CL_OUT") (pintype "bidirectional"))
      (node (ref "U$29") (pin "C_IN") (pinfunction "CI_C_IN") (pintype "bidirectional"))
    )
    (net (code "70") (name "Net-(U$28-DO)") (class "Default")
      (node (ref "U$28") (pin "D_OUT") (pinfunction "DO_D_OUT") (pintype "bidirectional"))
      (node (ref "U$29") (pin "D_IN") (pinfunction "DI_D_IN") (pintype "bidirectional"))
    )
    (net (code "71") (name "Net-(U$29-CO)") (class "Default")
      (node (ref "U$29") (pin "CL_OUT") (pinfunction "CO_CL_OUT") (pintype "bidirectional"))
      (node (ref "U$30") (pin "C_IN") (pinfunction "CI_C_IN") (pintype "bidirectional"))
    )
    (net (code "72") (name "Net-(U$29-DO)") (class "Default")
      (node (ref "U$29") (pin "D_OUT") (pinfunction "DO_D_OUT") (pintype "bidirectional"))
      (node (ref "U$30") (pin "D_IN") (pinfunction "DI_D_IN") (pintype "bidirectional"))
    )
    (net (code "73") (name "Net-(U$30-CO)") (class "Default")
      (node (ref "U$30") (pin "CL_OUT") (pinfunction "CO_CL_OUT") (pintype "bidirectional"))
      (node (ref "U$31") (pin "C_IN") (pinfunction "CI_C_IN") (pintype "bidirectional"))
    )
    (net (code "74") (name "Net-(U$30-DO)") (class "Default")
      (node (ref "U$30") (pin "D_OUT") (pinfunction "DO_D_OUT") (pintype "bidirectional"))
      (node (ref "U$31") (pin "D_IN") (pinfunction "DI_D_IN") (pintype "bidirectional"))
    )
    (net (code "75") (name "VCC") (class "Default")
      (node (ref "JP1") (pin "2") (pinfunction "2_2") (pintype "passive"))
      (node (ref "S1") (pin "2") (pinfunction "P_2") (pintype "passive"))
    )
    (net (code "76") (name "unconnected-(JP3-Pad1)") (class "Default")
      (node (ref "JP3") (pin "1") (pinfunction "1_1") (pintype "passive"))
    )
    (net (code "77") (name "unconnected-(S1-S-Pad3)") (class "Default")
      (node (ref "S1") (pin "3") (pinfunction "S_3") (pintype "passive"))
    )
    (net (code "78") (name "unconnected-(U$4-BOOT0-Pad1)") (class "Default")
      (node (ref "U$4") (pin "1") (pinfunction "BOOT0_1") (pintype "bidirectional"))
    )
    (net (code "79") (name "unconnected-(U$4-PA9-Pad17)") (class "Default")
      (node (ref "U$4") (pin "17") (pinfunction "PA9_17") (pintype "bidirectional"))
    )
    (net (code "80") (name "unconnected-(U$4-PA10-Pad18)") (class "Default")
      (node (ref "U$4") (pin "18") (pinfunction "PA10_18") (pintype "bidirectional"))
    )
    (net (code "81") (name "unconnected-(U$4-PB1-Pad14)") (class "Default")
      (node (ref "U$4") (pin "14") (pinfunction "PB1_14") (pintype "bidirectional"))
    )
    (net (code "82") (name "unconnected-(U$4-PF0{slash}OSC_IN-Pad2)") (class "Default")
      (node (ref "U$4") (pin "2") (pinfunction "PF0/OSC_IN_2") (pintype "bidirectional"))
    )
    (net (code "83") (name "unconnected-(U$4-PF1{slash}OSC_OUT-Pad3)") (class "Default")
      (node (ref "U$4") (pin "3") (pinfunction "PF1/OSC_OUT_3") (pintype "bidirectional"))
    )
    (net (code "84") (name "unconnected-(U$26-CO-Pad2)") (class "Default")
      (node (ref "U$26") (pin "2") (pinfunction "CO_2") (pintype "bidirectional"))
    )
    (net (code "85") (name "unconnected-(U$26-DO-Pad3)") (class "Default")
      (node (ref "U$26") (pin "3") (pinfunction "DO_3") (pintype "bidirectional"))
    )
  )
)
